# v2_esp12-adapter.net
KiCad netlist of a schematic drawn in EAGLE
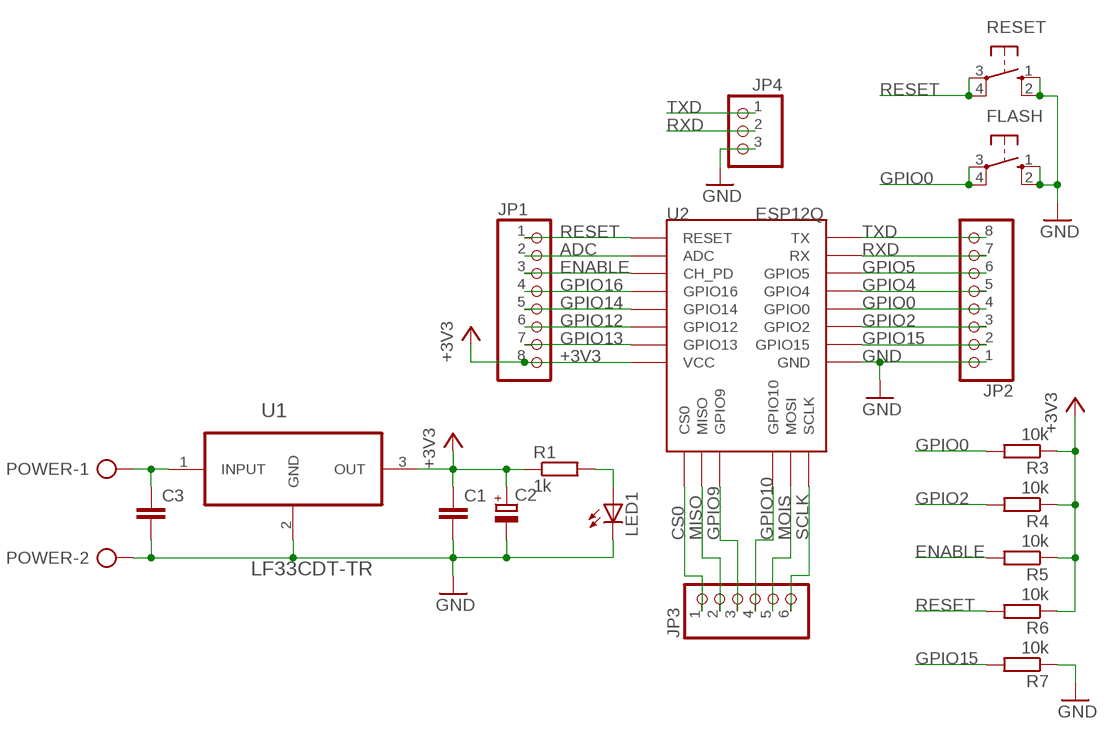
[diagram p0: schematic, sheet 1]

(export (version "E")
  (design (tool "Eeschema 10.0.6"))
  (components
    (comp (ref "C1")
      (value "C-EU025-025X050")
      (footprint "eagle-import:C025-025X050")
      (libsource (lib "eagle-import") (part "C-EU025-025X050"))
    )
    (comp (ref "C2")
      (value "CPOL-EUE2,5-6E")
      (footprint "eagle-import:E2,5-6E")
      (libsource (lib "eagle-import") (part "CPOL-EUE2,5-6E"))
    )
    (comp (ref "C3")
      (value "C-EU025-025X050")
      (footprint "eagle-import:C025-025X050")
      (libsource (lib "eagle-import") (part "C-EU025-025X050"))
    )
    (comp (ref "FLASH")
      (value "10-XX")
      (footprint "eagle-import:B3F-10XX")
      (fields (field (name "MPN") "B3F-1000"))
      (libsource (lib "eagle-import") (part "10-XX"))
    )
    (comp (ref "JP1")
      (value "PINHD-1X8")
      (footprint "eagle-import:1X08")
      (libsource (lib "eagle-import") (part "PINHD-1X8"))
    )
    (comp (ref "JP2")
      (value "PINHD-1X8")
      (footprint "eagle-import:1X08")
      (libsource (lib "eagle-import") (part "PINHD-1X8"))
    )
    (comp (ref "JP3")
      (value "PINHD-1X6")
      (footprint "eagle-import:1X06")
      (libsource (lib "eagle-import") (part "PINHD-1X6"))
    )
    (comp (ref "JP4")
      (value "PINHD-1X3/90")
      (footprint "eagle-import:1X03_90")
      (libsource (lib "eagle-import") (part "PINHD-1X3/90"))
    )
    (comp (ref "LED1")
      (value "LED5MM")
      (footprint "eagle-import:LED5MM")
      (libsource (lib "eagle-import") (part "LED5MM"))
    )
    (comp (ref "POWER")
      (value "AK300/2")
      (footprint "eagle-import:AK300_2")
      (libsource (lib "eagle-import") (part "AK300/2"))
    )
    (comp (ref "R1")
      (value "1k")
      (footprint "eagle-import:R1206")
      (libsource (lib "eagle-import") (part "R-EU_R1206"))
    )
    (comp (ref "R3")
      (value "10k")
      (footprint "eagle-import:R1206")
      (libsource (lib "eagle-import") (part "R-EU_R1206"))
    )
    (comp (ref "R4")
      (value "10k")
      (footprint "eagle-import:R1206")
      (libsource (lib "eagle-import") (part "R-EU_R1206"))
    )
    (comp (ref "R5")
      (value "10k")
      (footprint "eagle-import:R1206")
      (libsource (lib "eagle-import") (part "R-EU_R1206"))
    )
    (comp (ref "R6")
      (value "10k")
      (footprint "eagle-import:R1206")
      (libsource (lib "eagle-import") (part "R-EU_R1206"))
    )
    (comp (ref "R7")
      (value "10k")
      (footprint "eagle-import:R1206")
      (libsource (lib "eagle-import") (part "R-EU_R1206"))
    )
    (comp (ref "RESET")
      (value "10-XX")
      (footprint "eagle-import:B3F-10XX")
      (fields (field (name "MPN") "B3F-1000"))
      (libsource (lib "eagle-import") (part "10-XX"))
    )
    (comp (ref "U1")
      (value "LF33CDT-TR")
      (footprint "eagle-import:TO228P972X240-3N")
      (fields (field (name "MF") "STMicroelectronics"))
      (libsource (lib "eagle-import") (part "LF33CDT-TR"))
    )
    (comp (ref "U2")
      (value "ESP12Q")
      (footprint "eagle-import:ESP12Q")
      (libsource (lib "eagle-import") (part "ESP12Q"))
    )
  )
  (nets
    (net (code "1") (name "+3V3") (class "Default")
      (node (ref "C1") (pin "1") (pinfunction "1_1") (pintype "passive"))
      (node (ref "C2") (pin "+") (pinfunction "+_+") (pintype "passive"))
      (node (ref "JP1") (pin "8") (pinfunction "8_8") (pintype "passive"))
      (node (ref "R1") (pin "1") (pinfunction "1_1") (pintype "passive"))
      (node (ref "R3") (pin "1") (pinfunction "1_1") (pintype "passive"))
      (node (ref "R4") (pin "1") (pinfunction "1_1") (pintype "passive"))
      (node (ref "R5") (pin "1") (pinfunction "1_1") (pintype "passive"))
      (node (ref "R6") (pin "1") (pinfunction "1_1") (pintype "passive"))
      (node (ref "U1") (pin "3") (pinfunction "OUT_3") (pintype "output"))
      (node (ref "U2") (pin "VCC") (pinfunction "VCC_VCC") (pintype "bidirectional"))
    )
    (net (code "2") (name "/ADC") (class "Default")
      (node (ref "JP1") (pin "2") (pinfunction "2_2") (pintype "passive"))
      (node (ref "U2") (pin "ADC") (pinfunction "ADC_ADC") (pintype "bidirectional"))
    )
    (net (code "3") (name "/CS0") (class "Default")
      (node (ref "JP3") (pin "1") (pinfunction "1_1") (pintype "passive"))
      (node (ref "U2") (pin "CS0") (pinfunction "CS0_CS0") (pintype "bidirectional"))
    )
    (net (code "4") (name "/ENABLE") (class "Default")
      (node (ref "JP1") (pin "3") (pinfunction "3_3") (pintype "passive"))
      (node (ref "R5") (pin "2") (pinfunction "2_2") (pintype "passive"))
      (node (ref "U2") (pin "CH_PD") (pinfunction "CH_PD_CH_PD") (pintype "bidirectional"))
    )
    (net (code "5") (name "/GPIO0") (class "Default")
      (node (ref "FLASH") (pin "3") (pinfunction "P_3") (pintype "passive"))
      (node (ref "FLASH") (pin "4") (pinfunction "P1_4") (pintype "passive"))
      (node (ref "JP2") (pin "4") (pinfunction "4_4") (pintype "passive"))
      (node (ref "R3") (pin "2") (pinfunction "2_2") (pintype "passive"))
      (node (ref "U2") (pin "GPIO0") (pinfunction "GPIO0_GPIO0") (pintype "bidirectional"))
    )
    (net (code "6") (name "/GPIO2") (class "Default")
      (node (ref "JP2") (pin "3") (pinfunction "3_3") (pintype "passive"))
      (node (ref "R4") (pin "2") (pinfunction "2_2") (pintype "passive"))
      (node (ref "U2") (pin "GPIO2") (pinfunction "GPIO2_GPIO2") (pintype "bidirectional"))
    )
    (net (code "7") (name "/GPIO4") (class "Default")
      (node (ref "JP2") (pin "5") (pinfunction "5_5") (pintype "passive"))
      (node (ref "U2") (pin "GPIO5") (pinfunction "GPIO4_GPIO5") (pintype "bidirectional"))
    )
    (net (code "8") (name "/GPIO5") (class "Default")
      (node (ref "JP2") (pin "6") (pinfunction "6_6") (pintype "passive"))
      (node (ref "U2") (pin "GPIO4") (pinfunction "GPIO5_GPIO4") (pintype "bidirectional"))
    )
    (net (code "9") (name "/GPIO9") (class "Default")
      (node (ref "JP3") (pin "3") (pinfunction "3_3") (pintype "passive"))
      (node (ref "U2") (pin "GPIO9") (pinfunction "GPIO9_GPIO9") (pintype "bidirectional"))
    )
    (net (code "10") (name "/GPIO10") (class "Default")
      (node (ref "JP3") (pin "4") (pinfunction "4_4") (pintype "passive"))
      (node (ref "U2") (pin "GPIO10") (pinfunction "GPIO10_GPIO10") (pintype "bidirectional"))
    )
    (net (code "11") (name "/GPIO12") (class "Default")
      (node (ref "JP1") (pin "6") (pinfunction "6_6") (pintype "passive"))
      (node (ref "U2") (pin "GPIO12") (pinfunction "GPIO12_GPIO12") (pintype "bidirectional"))
    )
    (net (code "12") (name "/GPIO13") (class "Default")
      (node (ref "JP1") (pin "7") (pinfunction "7_7") (pintype "passive"))
      (node (ref "U2") (pin "GPIO13") (pinfunction "GPIO13_GPIO13") (pintype "bidirectional"))
    )
    (net (code "13") (name "/GPIO14") (class "Default")
      (node (ref "JP1") (pin "5") (pinfunction "5_5") (pintype "passive"))
      (node (ref "U2") (pin "GPIO14") (pinfunction "GPIO14_GPIO14") (pintype "bidirectional"))
    )
    (net (code "14") (name "/GPIO15") (class "Default")
      (node (ref "JP2") (pin "2") (pinfunction "2_2") (pintype "passive"))
      (node (ref "R7") (pin "2") (pinfunction "2_2") (pintype "passive"))
      (node (ref "U2") (pin "GPIO15") (pinfunction "GPIO15_GPIO15") (pintype "bidirectional"))
    )
    (net (code "15") (name "/GPIO16") (class "Default")
      (node (ref "JP1") (pin "4") (pinfunction "4_4") (pintype "passive"))
      (node (ref "U2") (pin "GPIO16") (pinfunction "GPIO16_GPIO16") (pintype "bidirectional"))
    )
    (net (code "16") (name "/MISO") (class "Default")
      (node (ref "JP3") (pin "2") (pinfunction "2_2") (pintype "passive"))
      (node (ref "U2") (pin "MISO") (pinfunction "MISO_MISO") (pintype "bidirectional"))
    )
    (net (code "17") (name "/MOIS") (class "Default")
      (node (ref "JP3") (pin "5") (pinfunction "5_5") (pintype "passive"))
      (node (ref "U2") (pin "MOSI") (pinfunction "MOSI_MOSI") (pintype "bidirectional"))
    )
    (net (code "18") (name "/RESET") (class "Default")
      (node (ref "JP1") (pin "1") (pinfunction "1_1") (pintype "passive"))
      (node (ref "R6") (pin "2") (pinfunction "2_2") (pintype "passive"))
      (node (ref "RESET") (pin "3") (pinfunction "P_3") (pintype "passive"))
      (node (ref "RESET") (pin "4") (pinfunction "P1_4") (pintype "passive"))
      (node (ref "U2") (pin "RESET") (pinfunction "RESET_RESET") (pintype "bidirectional"))
    )
    (net (code "19") (name "/RXD") (class "Default")
      (node (ref "JP2") (pin "7") (pinfunction "7_7") (pintype "passive"))
      (node (ref "JP4") (pin "2") (pinfunction "2_2") (pintype "passive"))
      (node (ref "U2") (pin "RX") (pinfunction "RX_RX") (pintype "bidirectional"))
    )
    (net (code "20") (name "/SCLK") (class "Default")
      (node (ref "JP3") (pin "6") (pinfunction "6_6") (pintype "passive"))
      (node (ref "U2") (pin "SCLK") (pinfunction "SCLK_SCLK") (pintype "bidirectional"))
    )
    (net (code "21") (name "/TXD") (class "Default")
      (node (ref "JP2") (pin "8") (pinfunction "8_8") (pintype "passive"))
      (node (ref "JP4") (pin "1") (pinfunction "1_1") (pintype "passive"))
      (node (ref "U2") (pin "TX") (pinfunction "TX_TX") (pintype "bidirectional"))
    )
    (net (code "22") (name "GND") (class "Default")
      (node (ref "C1") (pin "2") (pinfunction "2_2") (pintype "passive"))
      (node (ref "C2") (pin "-") (pinfunction "-_-") (pintype "passive"))
      (node (ref "C3") (pin "2") (pinfunction "2_2") (pintype "passive"))
      (node (ref "FLASH") (pin "1") (pinfunction "S_1") (pintype "passive"))
      (node (ref "FLASH") (pin "2") (pinfunction "S1_2") (pintype "passive"))
      (node (ref "JP2") (pin "1") (pinfunction "1_1") (pintype "passive"))
      (node (ref "JP4") (pin "3") (pinfunction "3_3") (pintype "passive"))
      (node (ref "LED1") (pin "K") (pinfunction "C_K") (pintype "passive"))
      (node (ref "POWER") (pin "2") (pinfunction "KL_2") (pintype "passive"))
      (node (ref "R7") (pin "1") (pinfunction "1_1") (pintype "passive"))
      (node (ref "RESET") (pin "1") (pinfunction "S_1") (pintype "passive"))
      (node (ref "RESET") (pin "2") (pinfunction "S1_2") (pintype "passive"))
      (node (ref "U1") (pin "2") (pinfunction "GND_2") (pintype "passive"))
      (node (ref "U2") (pin "GND") (pinfunction "GND_GND") (pintype "bidirectional"))
    )
    (net (code "23") (name "Net-(LED1-PadA)") (class "Default")
      (node (ref "LED1") (pin "A") (pinfunction "A_A") (pintype "passive"))
      (node (ref "R1") (pin "2") (pinfunction "2_2") (pintype "passive"))
    )
    (net (code "24") (name "Net-(POWERA-KL)") (class "Default")
      (node (ref "C3") (pin "1") (pinfunction "1_1") (pintype "passive"))
      (node (ref "POWER") (pin "1") (pinfunction "KL_1") (pintype "passive"))
      (node (ref "U1") (pin "1") (pinfunction "INPUT_1") (pintype "input"))
    )
  )
)
